# backboard.net
KiCad netlist of a schematic drawn in EAGLE
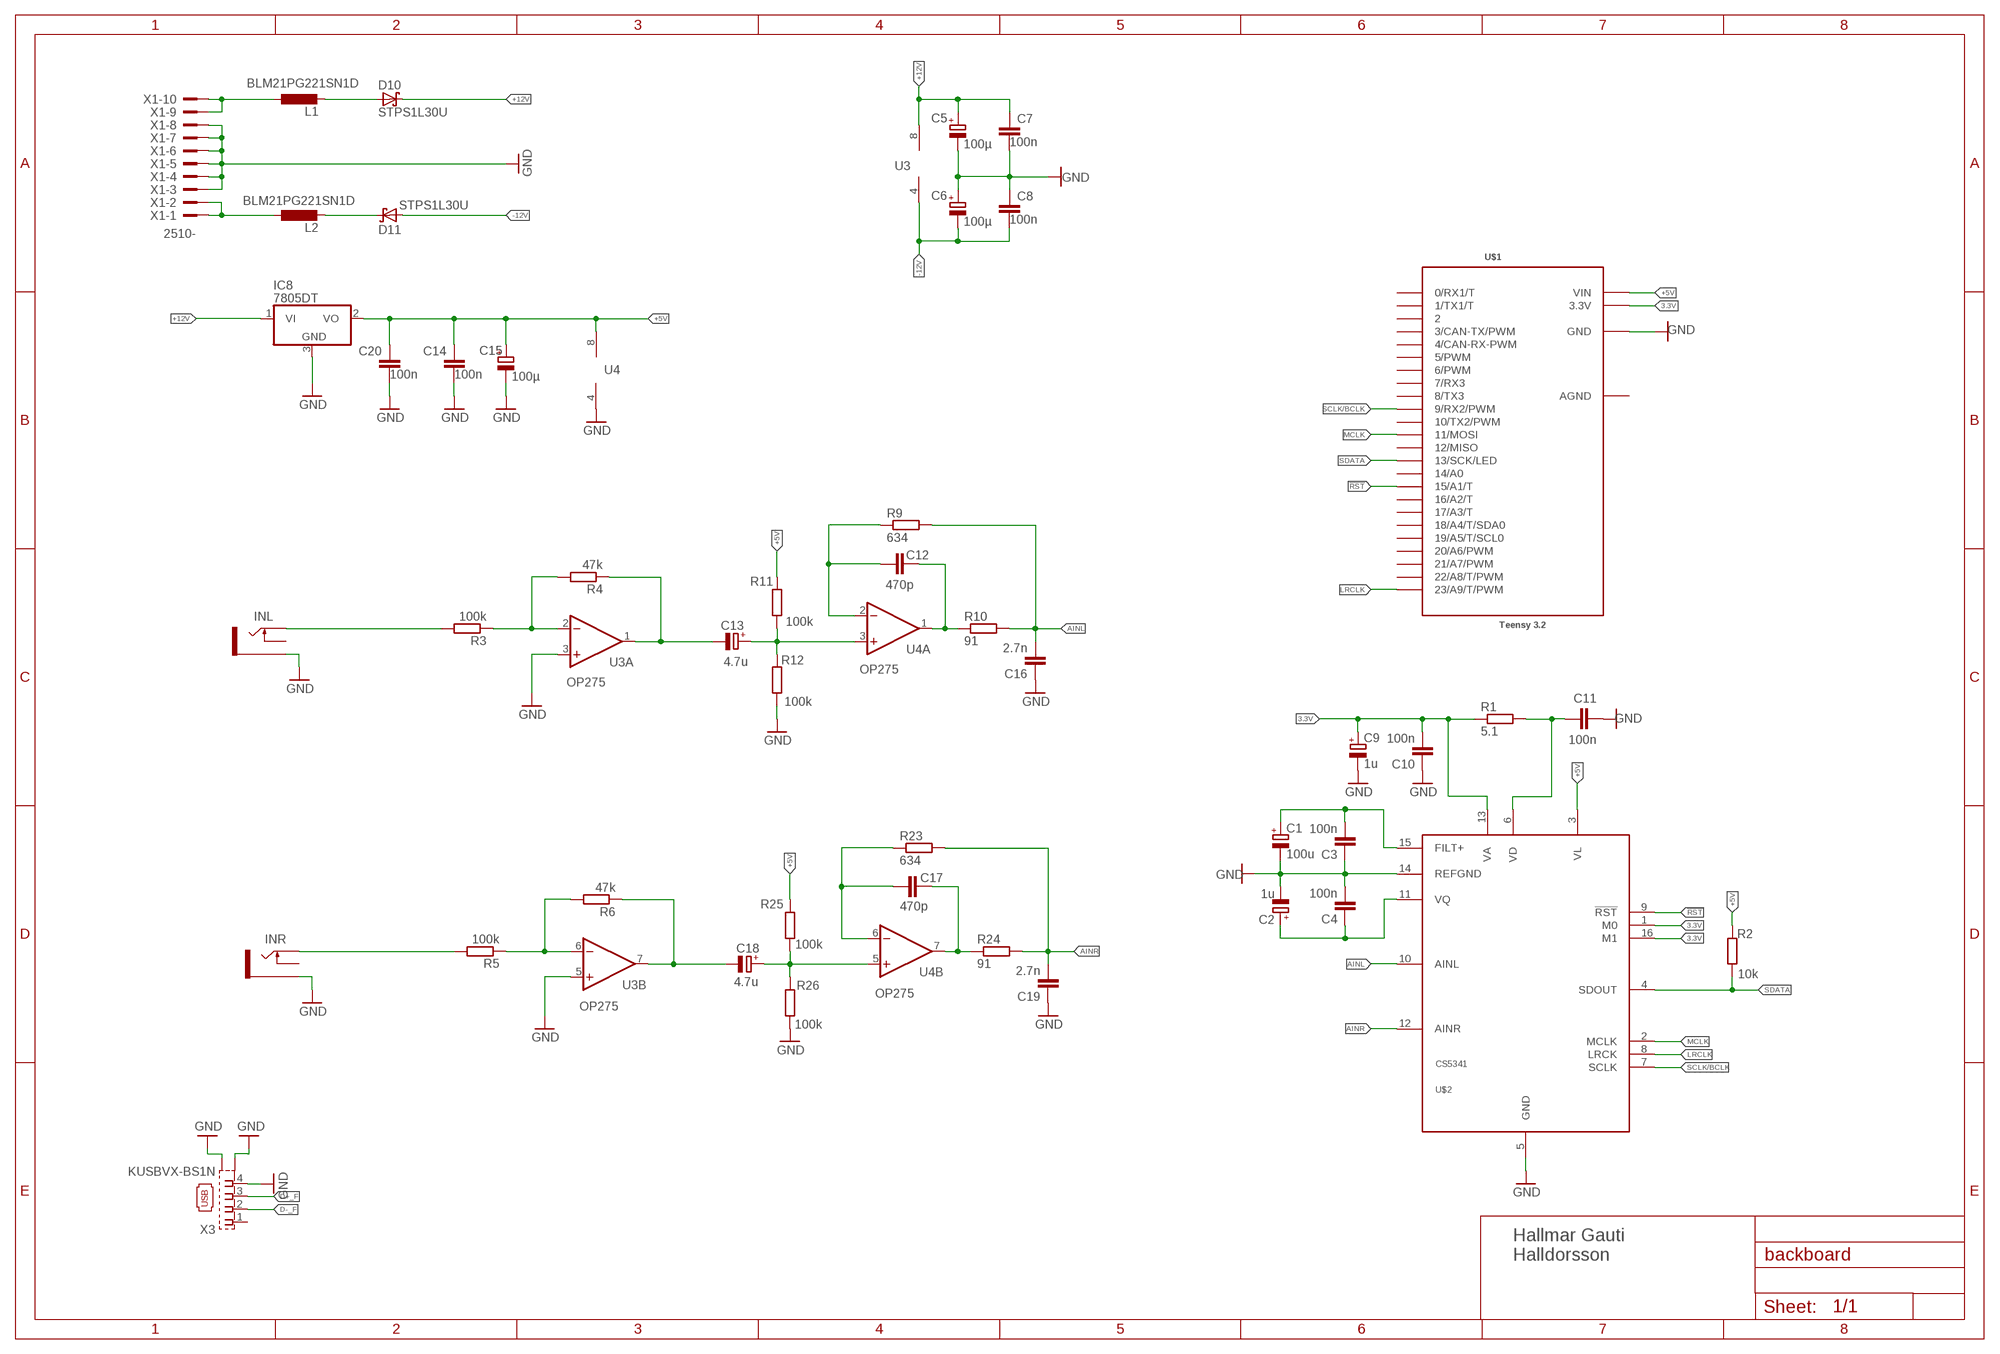
[diagram p0: schematic, sheet 1]

(export (version "E")
  (design (tool "Eeschema 10.0.6"))
  (components
    (comp (ref "C1")
      (value "100u")
      (footprint "eagle-import:153CLV-0605")
      (libsource (lib "eagle-import") (part "CPOL-EU153CLV-0605"))
    )
    (comp (ref "C2")
      (value "1u")
      (footprint "eagle-import:153CLV-0405")
      (libsource (lib "eagle-import") (part "CPOL-EU153CLV-0405"))
    )
    (comp (ref "C3")
      (value "100n")
      (footprint "eagle-import:C0805")
      (libsource (lib "eagle-import") (part "C-EUC0805"))
    )
    (comp (ref "C4")
      (value "100n")
      (footprint "eagle-import:C0805")
      (libsource (lib "eagle-import") (part "C-EUC0805"))
    )
    (comp (ref "C5")
      (value "100µ")
      (footprint "eagle-import:153CLV-0505")
      (libsource (lib "eagle-import") (part "CPOL-EU153CLV-0505"))
    )
    (comp (ref "C6")
      (value "100µ")
      (footprint "eagle-import:153CLV-0505")
      (libsource (lib "eagle-import") (part "CPOL-EU153CLV-0505"))
    )
    (comp (ref "C7")
      (value "100n")
      (footprint "eagle-import:C0805")
      (libsource (lib "eagle-import") (part "C-EUC0805"))
    )
    (comp (ref "C8")
      (value "100n")
      (footprint "eagle-import:C0805")
      (libsource (lib "eagle-import") (part "C-EUC0805"))
    )
    (comp (ref "C9")
      (value "1u")
      (footprint "eagle-import:153CLV-0405")
      (libsource (lib "eagle-import") (part "CPOL-EU153CLV-0405"))
    )
    (comp (ref "C10")
      (value "100n")
      (footprint "eagle-import:C0805")
      (libsource (lib "eagle-import") (part "C-EUC0805"))
    )
    (comp (ref "C11")
      (value "100n")
      (footprint "eagle-import:C0805")
      (libsource (lib "eagle-import") (part "C-EUC0805"))
    )
    (comp (ref "C12")
      (value "470p")
      (footprint "eagle-import:C0805")
      (libsource (lib "eagle-import") (part "C-EUC0805"))
    )
    (comp (ref "C13")
      (value "4.7u")
      (footprint "eagle-import:153CLV-0405")
      (libsource (lib "eagle-import") (part "CPOL-EU153CLV-0405"))
    )
    (comp (ref "C14")
      (value "100n")
      (footprint "eagle-import:C0805")
      (libsource (lib "eagle-import") (part "C-EUC0805"))
    )
    (comp (ref "C15")
      (value "100µ")
      (footprint "eagle-import:153CLV-0505")
      (libsource (lib "eagle-import") (part "CPOL-EU153CLV-0505"))
    )
    (comp (ref "C16")
      (value "2.7n")
      (footprint "eagle-import:C0805")
      (libsource (lib "eagle-import") (part "C-EUC0805"))
    )
    (comp (ref "C17")
      (value "470p")
      (footprint "eagle-import:C0805")
      (libsource (lib "eagle-import") (part "C-EUC0805"))
    )
    (comp (ref "C18")
      (value "4.7u")
      (footprint "eagle-import:153CLV-0405")
      (libsource (lib "eagle-import") (part "CPOL-EU153CLV-0405"))
    )
    (comp (ref "C19")
      (value "2.7n")
      (footprint "eagle-import:C0805")
      (libsource (lib "eagle-import") (part "C-EUC0805"))
    )
    (comp (ref "C20")
      (value "100n")
      (footprint "eagle-import:C0805")
      (libsource (lib "eagle-import") (part "C-EUC0805"))
    )
    (comp (ref "D10")
      (value "STPS1L30U")
      (footprint "eagle-import:SMB")
      (libsource (lib "eagle-import") (part "MBRS130LT3"))
    )
    (comp (ref "D11")
      (value "STPS1L30U")
      (footprint "eagle-import:SMB")
      (libsource (lib "eagle-import") (part "MBRS130LT3"))
    )
    (comp (ref "IC8")
      (value "7805DT")
      (footprint "eagle-import:TO252")
      (libsource (lib "eagle-import") (part "78DT05"))
    )
    (comp (ref "INL")
      (value "THONKICONN16PJ138")
      (footprint "eagle-import:WQP-PJ301M-12_JACK")
      (libsource (lib "eagle-import") (part "THONKICONN16PJ138"))
    )
    (comp (ref "INR")
      (value "THONKICONN16PJ138")
      (footprint "eagle-import:WQP-PJ301M-12_JACK")
      (libsource (lib "eagle-import") (part "THONKICONN16PJ138"))
    )
    (comp (ref "L1")
      (value "BLM21PG221SN1D")
      (footprint "eagle-import:L2012C")
      (libsource (lib "eagle-import") (part "L-EUL2012C"))
    )
    (comp (ref "L2")
      (value "BLM21PG221SN1D")
      (footprint "eagle-import:L2012C")
      (libsource (lib "eagle-import") (part "L-EUL2012C"))
    )
    (comp (ref "R1")
      (value "5.1")
      (footprint "eagle-import:M0805")
      (libsource (lib "eagle-import") (part "R-EU_M0805"))
    )
    (comp (ref "R2")
      (value "10k")
      (footprint "eagle-import:M0805")
      (libsource (lib "eagle-import") (part "R-EU_M0805"))
    )
    (comp (ref "R3")
      (value "100k")
      (footprint "eagle-import:M0805")
      (libsource (lib "eagle-import") (part "R-EU_M0805"))
    )
    (comp (ref "R4")
      (value "47k")
      (footprint "eagle-import:M0805")
      (libsource (lib "eagle-import") (part "R-EU_M0805"))
    )
    (comp (ref "R5")
      (value "100k")
      (footprint "eagle-import:M0805")
      (libsource (lib "eagle-import") (part "R-EU_M0805"))
    )
    (comp (ref "R6")
      (value "47k")
      (footprint "eagle-import:M0805")
      (libsource (lib "eagle-import") (part "R-EU_M0805"))
    )
    (comp (ref "R9")
      (value "634")
      (footprint "eagle-import:M0805")
      (libsource (lib "eagle-import") (part "R-EU_M0805"))
    )
    (comp (ref "R10")
      (value "91")
      (footprint "eagle-import:M0805")
      (libsource (lib "eagle-import") (part "R-EU_M0805"))
    )
    (comp (ref "R11")
      (value "100k")
      (footprint "eagle-import:M0805")
      (libsource (lib "eagle-import") (part "R-EU_M0805"))
    )
    (comp (ref "R12")
      (value "100k")
      (footprint "eagle-import:M0805")
      (libsource (lib "eagle-import") (part "R-EU_M0805"))
    )
    (comp (ref "R23")
      (value "634")
      (footprint "eagle-import:M0805")
      (libsource (lib "eagle-import") (part "R-EU_M0805"))
    )
    (comp (ref "R24")
      (value "91")
      (footprint "eagle-import:M0805")
      (libsource (lib "eagle-import") (part "R-EU_M0805"))
    )
    (comp (ref "R25")
      (value "100k")
      (footprint "eagle-import:M0805")
      (libsource (lib "eagle-import") (part "R-EU_M0805"))
    )
    (comp (ref "R26")
      (value "100k")
      (footprint "eagle-import:M0805")
      (libsource (lib "eagle-import") (part "R-EU_M0805"))
    )
    (comp (ref "U$1")
      (value "Teensy 3.2")
      (footprint "eagle-import:TEENSY3.2_BAREBONES")
      (libsource (lib "eagle-import") (part "TEENSY3.2.BAREBONES"))
    )
    (comp (ref "U$2")
      (value "CS5341")
      (footprint "eagle-import:TSSOP16")
      (libsource (lib "eagle-import") (part "CS5341"))
    )
    (comp (ref "U3")
      (value "OP275")
      (footprint "eagle-import:SO08")
      (libsource (lib "eagle-import") (part "TL072_SMD"))
    )
    (comp (ref "U4")
      (value "OP275")
      (footprint "eagle-import:SO08")
      (libsource (lib "eagle-import") (part "TL072_SMD"))
    )
    (comp (ref "X1")
      (value "2510-")
      (footprint "eagle-import:PAK100_2500-10")
      (fields (field (name "MF") "3M") (field (name "MPN") "2510-6002UB"))
      (libsource (lib "eagle-import") (part "2510-"))
    )
    (comp (ref "X3")
      (value "KUSBVX-BS1N")
      (footprint "eagle-import:KUSBVX-BS1N")
      (libsource (lib "eagle-import") (part "KUSBVX-BS1N"))
    )
  )
  (nets
    (net (code "1") (name "+5V") (class "Default")
      (node (ref "C14") (pin "1") (pinfunction "1_1") (pintype "passive"))
      (node (ref "C15") (pin "+") (pinfunction "+_+") (pintype "passive"))
      (node (ref "C20") (pin "1") (pinfunction "1_1") (pintype "passive"))
      (node (ref "IC8") (pin "2") (pinfunction "VO_2") (pintype "passive"))
      (node (ref "R11") (pin "2") (pinfunction "2_2") (pintype "passive"))
      (node (ref "R2") (pin "2") (pinfunction "2_2") (pintype "passive"))
      (node (ref "R25") (pin "2") (pinfunction "2_2") (pintype "passive"))
      (node (ref "U$1") (pin "VIN") (pinfunction "VIN_VIN") (pintype "power_in"))
      (node (ref "U$2") (pin "3") (pinfunction "VL_3") (pintype "bidirectional"))
      (node (ref "U4") (pin "8") (pinfunction "V+_8") (pintype "power_in"))
    )
    (net (code "2") (name "+12V") (class "Default")
      (node (ref "C5") (pin "+") (pinfunction "+_+") (pintype "passive"))
      (node (ref "C7") (pin "1") (pinfunction "1_1") (pintype "passive"))
      (node (ref "D10") (pin "C") (pinfunction "C_C") (pintype "passive"))
      (node (ref "IC8") (pin "1") (pinfunction "VI_1") (pintype "input"))
      (node (ref "U3") (pin "8") (pinfunction "V+_8") (pintype "power_in"))
    )
    (net (code "3") (name "-12V") (class "Default")
      (node (ref "C6") (pin "-") (pinfunction "-_-") (pintype "passive"))
      (node (ref "C8") (pin "2") (pinfunction "2_2") (pintype "passive"))
      (node (ref "D11") (pin "A") (pinfunction "A_A") (pintype "passive"))
      (node (ref "U3") (pin "4") (pinfunction "V-_4") (pintype "power_in"))
    )
    (net (code "4") (name "/AGND") (class "Default")
      (node (ref "U$1") (pin "AGND") (pinfunction "AGND_AGND") (pintype "power_in"))
    )
    (net (code "5") (name "/~{RST}") (class "Default")
      (node (ref "U$1") (pin "15/A1") (pinfunction "15/A1/T_15/A1") (pintype "bidirectional"))
      (node (ref "U$2") (pin "9") (pinfunction "~{RST}_9") (pintype "bidirectional"))
    )
    (net (code "6") (name "3.3V") (class "Default")
      (node (ref "C10") (pin "2") (pinfunction "2_2") (pintype "passive"))
      (node (ref "C9") (pin "+") (pinfunction "+_+") (pintype "passive"))
      (node (ref "R1") (pin "1") (pinfunction "1_1") (pintype "passive"))
      (node (ref "U$1") (pin "3.3V") (pinfunction "3.3V_3.3V") (pintype "power_in"))
      (node (ref "U$2") (pin "1") (pinfunction "M0_1") (pintype "bidirectional"))
      (node (ref "U$2") (pin "13") (pinfunction "VA_13") (pintype "bidirectional"))
      (node (ref "U$2") (pin "16") (pinfunction "M1_16") (pintype "bidirectional"))
    )
    (net (code "7") (name "AINL") (class "Default")
      (node (ref "C16") (pin "2") (pinfunction "2_2") (pintype "passive"))
      (node (ref "R10") (pin "2") (pinfunction "2_2") (pintype "passive"))
      (node (ref "R9") (pin "2") (pinfunction "2_2") (pintype "passive"))
      (node (ref "U$2") (pin "10") (pinfunction "AINL_10") (pintype "bidirectional"))
    )
    (net (code "8") (name "AINR") (class "Default")
      (node (ref "C19") (pin "2") (pinfunction "2_2") (pintype "passive"))
      (node (ref "R23") (pin "2") (pinfunction "2_2") (pintype "passive"))
      (node (ref "R24") (pin "2") (pinfunction "2_2") (pintype "passive"))
      (node (ref "U$2") (pin "12") (pinfunction "AINR_12") (pintype "bidirectional"))
    )
    (net (code "9") (name "D+_F") (class "Default")
      (node (ref "X3") (pin "3") (pinfunction "3_3") (pintype "passive"))
    )
    (net (code "10") (name "D-_F") (class "Default")
      (node (ref "X3") (pin "2") (pinfunction "2_2") (pintype "passive"))
    )
    (net (code "11") (name "GND") (class "Default")
      (node (ref "C1") (pin "-") (pinfunction "-_-") (pintype "passive"))
      (node (ref "C10") (pin "1") (pinfunction "1_1") (pintype "passive"))
      (node (ref "C11") (pin "1") (pinfunction "1_1") (pintype "passive"))
      (node (ref "C14") (pin "2") (pinfunction "2_2") (pintype "passive"))
      (node (ref "C15") (pin "-") (pinfunction "-_-") (pintype "passive"))
      (node (ref "C16") (pin "1") (pinfunction "1_1") (pintype "passive"))
      (node (ref "C19") (pin "1") (pinfunction "1_1") (pintype "passive"))
      (node (ref "C2") (pin "-") (pinfunction "-_-") (pintype "passive"))
      (node (ref "C20") (pin "2") (pinfunction "2_2") (pintype "passive"))
      (node (ref "C3") (pin "1") (pinfunction "1_1") (pintype "passive"))
      (node (ref "C4") (pin "2") (pinfunction "2_2") (pintype "passive"))
      (node (ref "C5") (pin "-") (pinfunction "-_-") (pintype "passive"))
      (node (ref "C6") (pin "+") (pinfunction "+_+") (pintype "passive"))
      (node (ref "C7") (pin "2") (pinfunction "2_2") (pintype "passive"))
      (node (ref "C8") (pin "1") (pinfunction "1_1") (pintype "passive"))
      (node (ref "C9") (pin "-") (pinfunction "-_-") (pintype "passive"))
      (node (ref "IC8") (pin "3") (pinfunction "GND_3") (pintype "passive"))
      (node (ref "INL") (pin "P$3_SLEEVE") (pinfunction "SLEEVE_P$3_SLEEVE") (pintype "passive"))
      (node (ref "INR") (pin "P$3_SLEEVE") (pinfunction "SLEEVE_P$3_SLEEVE") (pintype "passive"))
      (node (ref "R12") (pin "1") (pinfunction "1_1") (pintype "passive"))
      (node (ref "R26") (pin "1") (pinfunction "1_1") (pintype "passive"))
      (node (ref "U$1") (pin "GND") (pinfunction "GND_GND") (pintype "power_in"))
      (node (ref "U$2") (pin "14") (pinfunction "REFGND_14") (pintype "bidirectional"))
      (node (ref "U$2") (pin "5") (pinfunction "GND_5") (pintype "bidirectional"))
      (node (ref "U3") (pin "3") (pinfunction "+IN_3") (pintype "input"))
      (node (ref "U3") (pin "5") (pinfunction "+IN_5") (pintype "input"))
      (node (ref "U4") (pin "4") (pinfunction "V-_4") (pintype "power_in"))
      (node (ref "X1") (pin "3") (pinfunction "KL_3") (pintype "passive"))
      (node (ref "X1") (pin "4") (pinfunction "KL_4") (pintype "passive"))
      (node (ref "X1") (pin "5") (pinfunction "KL_5") (pintype "passive"))
      (node (ref "X1") (pin "6") (pinfunction "KL_6") (pintype "passive"))
      (node (ref "X1") (pin "7") (pinfunction "KL_7") (pintype "passive"))
      (node (ref "X1") (pin "8") (pinfunction "KL_8") (pintype "passive"))
      (node (ref "X3") (pin "4") (pinfunction "4_4") (pintype "passive"))
      (node (ref "X3") (pin "M1") (pinfunction "S1_M1") (pintype "passive"))
      (node (ref "X3") (pin "M2") (pinfunction "S2_M2") (pintype "passive"))
    )
    (net (code "12") (name "LRCLK") (class "Default")
      (node (ref "U$1") (pin "23/A9") (pinfunction "23/A9/T/PWM_23/A9") (pintype "bidirectional"))
      (node (ref "U$2") (pin "8") (pinfunction "LRCK_8") (pintype "bidirectional"))
    )
    (net (code "13") (name "MCLK") (class "Default")
      (node (ref "U$1") (pin "11") (pinfunction "11/MOSI_11") (pintype "bidirectional"))
      (node (ref "U$2") (pin "2") (pinfunction "MCLK_2") (pintype "bidirectional"))
    )
    (net (code "14") (name "Net-(D10-PadA)") (class "Default")
      (node (ref "D10") (pin "A") (pinfunction "A_A") (pintype "passive"))
      (node (ref "L1") (pin "2") (pinfunction "2_2") (pintype "passive"))
    )
    (net (code "15") (name "Net-(D11-PadC)") (class "Default")
      (node (ref "D11") (pin "C") (pinfunction "C_C") (pintype "passive"))
      (node (ref "L2") (pin "2") (pinfunction "2_2") (pintype "passive"))
    )
    (net (code "16") (name "Net-(INL-TIP)") (class "Default")
      (node (ref "INL") (pin "P$1_TIP") (pinfunction "TIP_P$1_TIP") (pintype "passive"))
      (node (ref "R3") (pin "2") (pinfunction "2_2") (pintype "passive"))
    )
    (net (code "17") (name "Net-(INR-TIP)") (class "Default")
      (node (ref "INR") (pin "P$1_TIP") (pinfunction "TIP_P$1_TIP") (pintype "passive"))
      (node (ref "R5") (pin "2") (pinfunction "2_2") (pintype "passive"))
    )
    (net (code "18") (name "Net-(U$2-FILT+)") (class "Default")
      (node (ref "C1") (pin "+") (pinfunction "+_+") (pintype "passive"))
      (node (ref "C3") (pin "2") (pinfunction "2_2") (pintype "passive"))
      (node (ref "U$2") (pin "15") (pinfunction "FILT+_15") (pintype "bidirectional"))
    )
    (net (code "19") (name "Net-(U$2-VD)") (class "Default")
      (node (ref "C11") (pin "2") (pinfunction "2_2") (pintype "passive"))
      (node (ref "R1") (pin "2") (pinfunction "2_2") (pintype "passive"))
      (node (ref "U$2") (pin "6") (pinfunction "VD_6") (pintype "bidirectional"))
    )
    (net (code "20") (name "Net-(U$2-VQ)") (class "Default")
      (node (ref "C2") (pin "+") (pinfunction "+_+") (pintype "passive"))
      (node (ref "C4") (pin "1") (pinfunction "1_1") (pintype "passive"))
      (node (ref "U$2") (pin "11") (pinfunction "VQ_11") (pintype "bidirectional"))
    )
    (net (code "21") (name "Net-(U3A--IN)") (class "Default")
      (node (ref "R3") (pin "1") (pinfunction "1_1") (pintype "passive"))
      (node (ref "R4") (pin "2") (pinfunction "2_2") (pintype "passive"))
      (node (ref "U3") (pin "2") (pinfunction "-IN_2") (pintype "input"))
    )
    (net (code "22") (name "Net-(U3A-OUT)") (class "Default")
      (node (ref "C13") (pin "-") (pinfunction "-_-") (pintype "passive"))
      (node (ref "R4") (pin "1") (pinfunction "1_1") (pintype "passive"))
      (node (ref "U3") (pin "1") (pinfunction "OUT_1") (pintype "output"))
    )
    (net (code "23") (name "Net-(U3B--IN)") (class "Default")
      (node (ref "R5") (pin "1") (pinfunction "1_1") (pintype "passive"))
      (node (ref "R6") (pin "2") (pinfunction "2_2") (pintype "passive"))
      (node (ref "U3") (pin "6") (pinfunction "-IN_6") (pintype "input"))
    )
    (net (code "24") (name "Net-(U3B-OUT)") (class "Default")
      (node (ref "C18") (pin "-") (pinfunction "-_-") (pintype "passive"))
      (node (ref "R6") (pin "1") (pinfunction "1_1") (pintype "passive"))
      (node (ref "U3") (pin "7") (pinfunction "OUT_7") (pintype "output"))
    )
    (net (code "25") (name "Net-(U4A-+IN)") (class "Default")
      (node (ref "C13") (pin "+") (pinfunction "+_+") (pintype "passive"))
      (node (ref "R11") (pin "1") (pinfunction "1_1") (pintype "passive"))
      (node (ref "R12") (pin "2") (pinfunction "2_2") (pintype "passive"))
      (node (ref "U4") (pin "3") (pinfunction "+IN_3") (pintype "input"))
    )
    (net (code "26") (name "Net-(U4A--IN)") (class "Default")
      (node (ref "C12") (pin "2") (pinfunction "2_2") (pintype "passive"))
      (node (ref "R9") (pin "1") (pinfunction "1_1") (pintype "passive"))
      (node (ref "U4") (pin "2") (pinfunction "-IN_2") (pintype "input"))
    )
    (net (code "27") (name "Net-(U4A-OUT)") (class "Default")
      (node (ref "C12") (pin "1") (pinfunction "1_1") (pintype "passive"))
      (node (ref "R10") (pin "1") (pinfunction "1_1") (pintype "passive"))
      (node (ref "U4") (pin "1") (pinfunction "OUT_1") (pintype "output"))
    )
    (net (code "28") (name "Net-(U4B-+IN)") (class "Default")
      (node (ref "C18") (pin "+") (pinfunction "+_+") (pintype "passive"))
      (node (ref "R25") (pin "1") (pinfunction "1_1") (pintype "passive"))
      (node (ref "R26") (pin "2") (pinfunction "2_2") (pintype "passive"))
      (node (ref "U4") (pin "5") (pinfunction "+IN_5") (pintype "input"))
    )
    (net (code "29") (name "Net-(U4B--IN)") (class "Default")
      (node (ref "C17") (pin "2") (pinfunction "2_2") (pintype "passive"))
      (node (ref "R23") (pin "1") (pinfunction "1_1") (pintype "passive"))
      (node (ref "U4") (pin "6") (pinfunction "-IN_6") (pintype "input"))
    )
    (net (code "30") (name "Net-(U4B-OUT)") (class "Default")
      (node (ref "C17") (pin "1") (pinfunction "1_1") (pintype "passive"))
      (node (ref "R24") (pin "1") (pinfunction "1_1") (pintype "passive"))
      (node (ref "U4") (pin "7") (pinfunction "OUT_7") (pintype "output"))
    )
    (net (code "31") (name "Net-(X1A-KL)") (class "Default")
      (node (ref "L2") (pin "1") (pinfunction "1_1") (pintype "passive"))
      (node (ref "X1") (pin "1") (pinfunction "KL_1") (pintype "passive"))
      (node (ref "X1") (pin "2") (pinfunction "KL_2") (pintype "passive"))
    )
    (net (code "32") (name "Net-(X1B-KL)") (class "Default")
      (node (ref "L1") (pin "1") (pinfunction "1_1") (pintype "passive"))
      (node (ref "X1") (pin "10") (pinfunction "KL_10") (pintype "passive"))
      (node (ref "X1") (pin "9") (pinfunction "KL_9") (pintype "passive"))
    )
    (net (code "33") (name "SCLK{slash}BCLK") (class "Default")
      (node (ref "U$1") (pin "9") (pinfunction "9/RX2/PWM_9") (pintype "bidirectional"))
      (node (ref "U$2") (pin "7") (pinfunction "SCLK_7") (pintype "bidirectional"))
    )
    (net (code "34") (name "SDATA") (class "Default")
      (node (ref "R2") (pin "1") (pinfunction "1_1") (pintype "passive"))
      (node (ref "U$1") (pin "13") (pinfunction "13/SCK/LED_13") (pintype "bidirectional"))
      (node (ref "U$2") (pin "4") (pinfunction "SDOUT_4") (pintype "bidirectional"))
    )
    (net (code "35") (name "unconnected-(INL-SWITCH-PadP$2_SWITCH)") (class "Default")
      (node (ref "INL") (pin "P$2_SWITCH") (pinfunction "SWITCH_P$2_SWITCH") (pintype "passive"))
    )
    (net (code "36") (name "unconnected-(INR-SWITCH-PadP$2_SWITCH)") (class "Default")
      (node (ref "INR") (pin "P$2_SWITCH") (pinfunction "SWITCH_P$2_SWITCH") (pintype "passive"))
    )
    (net (code "37") (name "unconnected-(U$1-0{slash}RX1{slash}T-Pad0)") (class "Default")
      (node (ref "U$1") (pin "0") (pinfunction "0/RX1/T_0") (pintype "bidirectional"))
    )
    (net (code "38") (name "unconnected-(U$1-1{slash}TX1{slash}T-Pad1)") (class "Default")
      (node (ref "U$1") (pin "1") (pinfunction "1/TX1/T_1") (pintype "bidirectional"))
    )
    (net (code "39") (name "unconnected-(U$1-3{slash}CAN-TX{slash}PWM-Pad3)") (class "Default")
      (node (ref "U$1") (pin "3") (pinfunction "3/CAN-TX/PWM_3") (pintype "bidirectional"))
    )
    (net (code "40") (name "unconnected-(U$1-4{slash}CAN-RX-PWM-Pad4)") (class "Default")
      (node (ref "U$1") (pin "4") (pinfunction "4/CAN-RX-PWM_4") (pintype "bidirectional"))
    )
    (net (code "41") (name "unconnected-(U$1-5{slash}PWM-Pad5)") (class "Default")
      (node (ref "U$1") (pin "5") (pinfunction "5/PWM_5") (pintype "bidirectional"))
    )
    (net (code "42") (name "unconnected-(U$1-6{slash}PWM-Pad6)") (class "Default")
      (node (ref "U$1") (pin "6") (pinfunction "6/PWM_6") (pintype "bidirectional"))
    )
    (net (code "43") (name "unconnected-(U$1-7{slash}RX3-Pad7)") (class "Default")
      (node (ref "U$1") (pin "7") (pinfunction "7/RX3_7") (pintype "bidirectional"))
    )
    (net (code "44") (name "unconnected-(U$1-8{slash}TX3-Pad8)") (class "Default")
      (node (ref "U$1") (pin "8") (pinfunction "8/TX3_8") (pintype "bidirectional"))
    )
    (net (code "45") (name "unconnected-(U$1-10{slash}TX2{slash}PWM-Pad10)") (class "Default")
      (node (ref "U$1") (pin "10") (pinfunction "10/TX2/PWM_10") (pintype "bidirectional"))
    )
    (net (code "46") (name "unconnected-(U$1-12{slash}MISO-Pad12)") (class "Default")
      (node (ref "U$1") (pin "12") (pinfunction "12/MISO_12") (pintype "bidirectional"))
    )
    (net (code "47") (name "unconnected-(U$1-16{slash}A2{slash}T-Pad16{slash}A2)") (class "Default")
      (node (ref "U$1") (pin "16/A2") (pinfunction "16/A2/T_16/A2") (pintype "bidirectional"))
    )
    (net (code "48") (name "unconnected-(U$1-17{slash}A3{slash}T-Pad17{slash}A3)") (class "Default")
      (node (ref "U$1") (pin "17/A3") (pinfunction "17/A3/T_17/A3") (pintype "bidirectional"))
    )
    (net (code "49") (name "unconnected-(U$1-18{slash}A4{slash}T{slash}SDA0-Pad18{slash}A4)") (class "Default")
      (node (ref "U$1") (pin "18/A4") (pinfunction "18/A4/T/SDA0_18/A4") (pintype "bidirectional"))
    )
    (net (code "50") (name "unconnected-(U$1-19{slash}A5{slash}T{slash}SCL0-Pad19{slash}A5)") (class "Default")
      (node (ref "U$1") (pin "19/A5") (pinfunction "19/A5/T/SCL0_19/A5") (pintype "bidirectional"))
    )
    (net (code "51") (name "unconnected-(U$1-20{slash}A6{slash}PWM-Pad20{slash}A6)") (class "Default")
      (node (ref "U$1") (pin "20/A6") (pinfunction "20/A6/PWM_20/A6") (pintype "bidirectional"))
    )
    (net (code "52") (name "unconnected-(U$1-21{slash}A7{slash}PWM-Pad21{slash}A7)") (class "Default")
      (node (ref "U$1") (pin "21/A7") (pinfunction "21/A7/PWM_21/A7") (pintype "bidirectional"))
    )
    (net (code "53") (name "unconnected-(U$1-22{slash}A8{slash}T{slash}PWM-Pad22{slash}A8)") (class "Default")
      (node (ref "U$1") (pin "22/A8") (pinfunction "22/A8/T/PWM_22/A8") (pintype "bidirectional"))
    )
    (net (code "54") (name "unconnected-(U$1-Pad2)") (class "Default")
      (node (ref "U$1") (pin "2") (pinfunction "2_2") (pintype "bidirectional"))
    )
    (net (code "55") (name "unconnected-(U$1-Pad14{slash}A0)") (class "Default")
      (node (ref "U$1") (pin "14/A0") (pinfunction "14/A0_14/A0") (pintype "bidirectional"))
    )
    (net (code "56") (name "unconnected-(X3-Pad1)") (class "Default")
      (node (ref "X3") (pin "1") (pinfunction "1_1") (pintype "passive"))
    )
  )
)
